# transponder.net
KiCad netlist of a schematic drawn in EAGLE
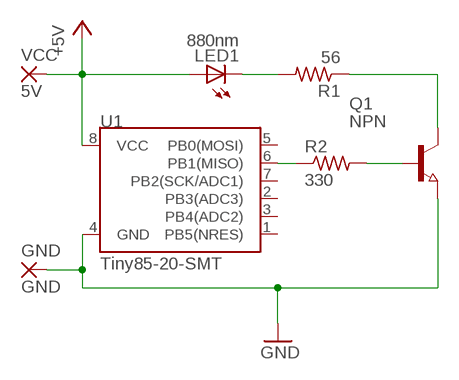
[diagram p0: schematic, sheet 1]

(export (version "E")
  (design (tool "Eeschema 10.0.6"))
  (components
    (comp (ref "GND")
      (value "GND")
      (footprint "eagle-import:SMD1,27-2,54")
      (libsource (lib "eagle-import") (part "SMD2"))
    )
    (comp (ref "LED1")
      (value "880nm")
      (footprint "eagle-import:LED3MM")
      (libsource (lib "eagle-import") (part "LED3MM"))
    )
    (comp (ref "Q1")
      (value "NPN")
      (footprint "eagle-import:SOT23")
      (libsource (lib "eagle-import") (part "NPN-TRANSISTOR_SOT23"))
    )
    (comp (ref "R1")
      (value "56")
      (footprint "eagle-import:R0603")
      (libsource (lib "eagle-import") (part "R-US_R0603"))
    )
    (comp (ref "R2")
      (value "330")
      (footprint "eagle-import:R0603")
      (libsource (lib "eagle-import") (part "R-US_R0603"))
    )
    (comp (ref "U1")
      (value "Tiny85-20-SMT")
      (footprint "eagle-import:SO08-EIAJ")
      (libsource (lib "eagle-import") (part "ATTINY45TINY85-20-SMT"))
    )
    (comp (ref "VCC")
      (value "5V")
      (footprint "eagle-import:SMD1,27-2,54")
      (libsource (lib "eagle-import") (part "SMD2"))
    )
  )
  (nets
    (net (code "1") (name "+5V") (class "Default")
      (node (ref "LED1") (pin "A") (pinfunction "A_A") (pintype "passive"))
      (node (ref "U1") (pin "8") (pinfunction "VCC_8") (pintype "bidirectional"))
      (node (ref "VCC") (pin "1") (pinfunction "P_1") (pintype "passive"))
    )
    (net (code "2") (name "GND") (class "Default")
      (node (ref "GND") (pin "1") (pinfunction "P_1") (pintype "passive"))
      (node (ref "Q1") (pin "2") (pinfunction "E_2") (pintype "passive"))
      (node (ref "U1") (pin "4") (pinfunction "GND_4") (pintype "bidirectional"))
    )
    (net (code "3") (name "Net-(LED1-C)") (class "Default")
      (node (ref "LED1") (pin "K") (pinfunction "C_K") (pintype "passive"))
      (node (ref "R1") (pin "2") (pinfunction "2_2") (pintype "passive"))
    )
    (net (code "4") (name "Net-(Q1-B)") (class "Default")
      (node (ref "Q1") (pin "1") (pinfunction "B_1") (pintype "passive"))
      (node (ref "R2") (pin "2") (pinfunction "2_2") (pintype "passive"))
    )
    (net (code "5") (name "Net-(Q1-C)") (class "Default")
      (node (ref "Q1") (pin "3") (pinfunction "C_3") (pintype "passive"))
      (node (ref "R1") (pin "1") (pinfunction "1_1") (pintype "passive"))
    )
    (net (code "6") (name "Net-(U1-PB1(MISO))") (class "Default")
      (node (ref "R2") (pin "1") (pinfunction "1_1") (pintype "passive"))
      (node (ref "U1") (pin "6") (pinfunction "PB1(MISO)_6") (pintype "bidirectional"))
    )
    (net (code "7") (name "unconnected-(U1-PB0(MOSI)-Pad5)") (class "Default")
      (node (ref "U1") (pin "5") (pinfunction "PB0(MOSI)_5") (pintype "bidirectional"))
    )
    (net (code "8") (name "unconnected-(U1-PB2(SCK{slash}ADC1)-Pad7)") (class "Default")
      (node (ref "U1") (pin "7") (pinfunction "PB2(SCK/ADC1)_7") (pintype "bidirectional"))
    )
    (net (code "9") (name "unconnected-(U1-PB3(ADC3)-Pad2)") (class "Default")
      (node (ref "U1") (pin "2") (pinfunction "PB3(ADC3)_2") (pintype "bidirectional"))
    )
    (net (code "10") (name "unconnected-(U1-PB4(ADC2)-Pad3)") (class "Default")
      (node (ref "U1") (pin "3") (pinfunction "PB4(ADC2)_3") (pintype "bidirectional"))
    )
    (net (code "11") (name "unconnected-(U1-PB5(NRES)-Pad1)") (class "Default")
      (node (ref "U1") (pin "1") (pinfunction "PB5(NRES)_1") (pintype "bidirectional"))
    )
  )
)
